# imager-adc.net
KiCad netlist of a schematic drawn in EAGLE
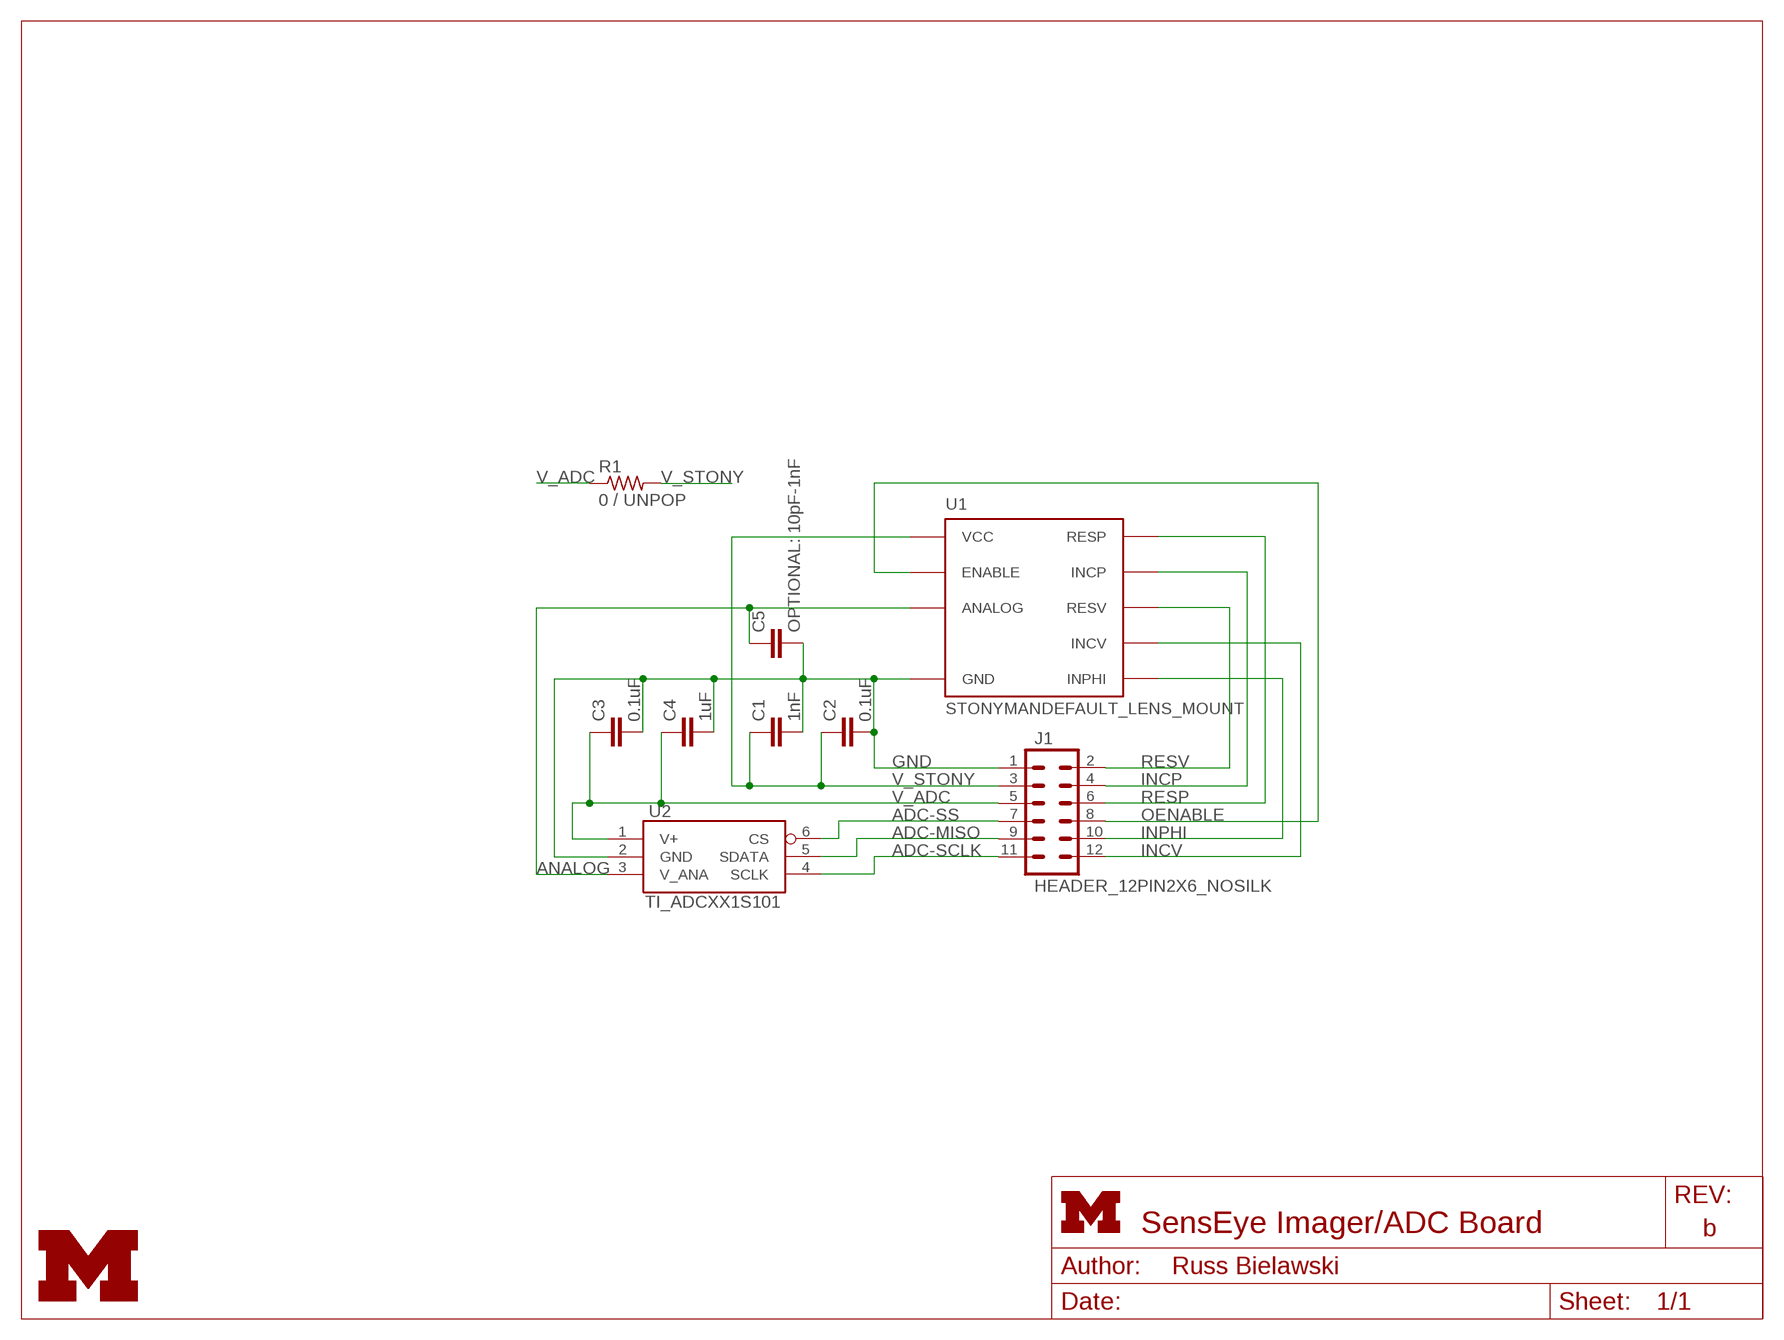
[diagram p0: schematic, sheet 1]

(export (version "E")
  (design (tool "Eeschema 10.0.6"))
  (components
    (comp (ref "C1")
      (value "1nF")
      (footprint "eagle-import:C0603")
      (libsource (lib "eagle-import") (part "C-EUC0603"))
    )
    (comp (ref "C2")
      (value "0.1uF")
      (footprint "eagle-import:C0603")
      (libsource (lib "eagle-import") (part "C-EUC0603"))
    )
    (comp (ref "C3")
      (value "0.1uF")
      (footprint "eagle-import:C0603")
      (libsource (lib "eagle-import") (part "C-EUC0603"))
    )
    (comp (ref "C4")
      (value "1uF")
      (footprint "eagle-import:C0603")
      (libsource (lib "eagle-import") (part "C-EUC0603"))
    )
    (comp (ref "C5")
      (value "OPTIONAL: 10pF-1nF")
      (footprint "eagle-import:C0603")
      (libsource (lib "eagle-import") (part "C-EUC0603"))
    )
    (comp (ref "J1")
      (value "HEADER_12PIN2X6_NOSILK")
      (footprint "eagle-import:HEADER2X6_0.05IN_NO_SILK")
      (libsource (lib "eagle-import") (part "HEADER_12PIN2X6_NOSILK"))
    )
    (comp (ref "R1")
      (value "0 / UNPOP")
      (footprint "eagle-import:R0603")
      (libsource (lib "eagle-import") (part "R-US_R0603"))
    )
    (comp (ref "U$1")
      (value "UMICH_SOLID_SMALL")
      (footprint "eagle-import:UMICH_SOLID_75MIL")
      (libsource (lib "eagle-import") (part "UMICH_SOLID_SMALL"))
    )
    (comp (ref "U1")
      (value "STONYMANDEFAULT_LENS_MOUNT")
      (footprint "eagle-import:STONYMAN_DEFAULT_LENS")
      (libsource (lib "eagle-import") (part "STONYMANDEFAULT_LENS_MOUNT"))
    )
    (comp (ref "U2")
      (value "TI_ADCXX1S101")
      (footprint "eagle-import:SOT23-6")
      (libsource (lib "eagle-import") (part "TI_ADCXX1S101"))
    )
  )
  (nets
    (net (code "1") (name "/ADC-MISO") (class "Default")
      (node (ref "J1") (pin "9") (pinfunction "9_9") (pintype "passive"))
      (node (ref "U2") (pin "5") (pinfunction "SDATA_5") (pintype "bidirectional"))
    )
    (net (code "2") (name "/ADC-SCLK") (class "Default")
      (node (ref "J1") (pin "11") (pinfunction "11_11") (pintype "passive"))
      (node (ref "U2") (pin "4") (pinfunction "SCLK_4") (pintype "bidirectional"))
    )
    (net (code "3") (name "/ADC-SS") (class "Default")
      (node (ref "J1") (pin "7") (pinfunction "7_7") (pintype "passive"))
      (node (ref "U2") (pin "6") (pinfunction "CS_6") (pintype "bidirectional"))
    )
    (net (code "4") (name "/ANALOG") (class "Default")
      (node (ref "C5") (pin "1") (pinfunction "1_1") (pintype "passive"))
      (node (ref "U1") (pin "P$8") (pinfunction "ANALOG_P$8") (pintype "output"))
      (node (ref "U2") (pin "3") (pinfunction "V_ANA_3") (pintype "bidirectional"))
    )
    (net (code "5") (name "/GND") (class "Default")
      (node (ref "C1") (pin "2") (pinfunction "2_2") (pintype "passive"))
      (node (ref "C2") (pin "2") (pinfunction "2_2") (pintype "passive"))
      (node (ref "C3") (pin "2") (pinfunction "2_2") (pintype "passive"))
      (node (ref "C4") (pin "2") (pinfunction "2_2") (pintype "passive"))
      (node (ref "C5") (pin "2") (pinfunction "2_2") (pintype "passive"))
      (node (ref "J1") (pin "1") (pinfunction "1_1") (pintype "passive"))
      (node (ref "U1") (pin "P$1") (pinfunction "GND_P$1") (pintype "power_in"))
      (node (ref "U1") (pin "P$10") (pinfunction "GND_P$10") (pintype "power_in"))
      (node (ref "U2") (pin "2") (pinfunction "GND_2") (pintype "bidirectional"))
    )
    (net (code "6") (name "/INCP") (class "Default")
      (node (ref "J1") (pin "4") (pinfunction "4_4") (pintype "passive"))
      (node (ref "U1") (pin "P$4") (pinfunction "INCP_P$4") (pintype "input"))
    )
    (net (code "7") (name "/INCV") (class "Default")
      (node (ref "J1") (pin "12") (pinfunction "12_12") (pintype "passive"))
      (node (ref "U1") (pin "P$6") (pinfunction "INCV_P$6") (pintype "input"))
    )
    (net (code "8") (name "/INPHI") (class "Default")
      (node (ref "J1") (pin "10") (pinfunction "10_10") (pintype "passive"))
      (node (ref "U1") (pin "P$7") (pinfunction "INPHI_P$7") (pintype "input"))
    )
    (net (code "9") (name "/OENABLE") (class "Default")
      (node (ref "J1") (pin "8") (pinfunction "8_8") (pintype "passive"))
      (node (ref "U1") (pin "P$9") (pinfunction "ENABLE_P$9") (pintype "input"))
    )
    (net (code "10") (name "/RESP") (class "Default")
      (node (ref "J1") (pin "6") (pinfunction "6_6") (pintype "passive"))
      (node (ref "U1") (pin "P$3") (pinfunction "RESP_P$3") (pintype "input"))
    )
    (net (code "11") (name "/RESV") (class "Default")
      (node (ref "J1") (pin "2") (pinfunction "2_2") (pintype "passive"))
      (node (ref "U1") (pin "P$5") (pinfunction "RESV_P$5") (pintype "input"))
    )
    (net (code "12") (name "/V_ADC") (class "Default")
      (node (ref "C3") (pin "1") (pinfunction "1_1") (pintype "passive"))
      (node (ref "C4") (pin "1") (pinfunction "1_1") (pintype "passive"))
      (node (ref "J1") (pin "5") (pinfunction "5_5") (pintype "passive"))
      (node (ref "R1") (pin "1") (pinfunction "1_1") (pintype "passive"))
      (node (ref "U2") (pin "1") (pinfunction "V+_1") (pintype "bidirectional"))
    )
    (net (code "13") (name "/V_STONY") (class "Default")
      (node (ref "C1") (pin "1") (pinfunction "1_1") (pintype "passive"))
      (node (ref "C2") (pin "1") (pinfunction "1_1") (pintype "passive"))
      (node (ref "J1") (pin "3") (pinfunction "3_3") (pintype "passive"))
      (node (ref "R1") (pin "2") (pinfunction "2_2") (pintype "passive"))
      (node (ref "U1") (pin "P$2") (pinfunction "VCC_P$2") (pintype "power_in"))
    )
  )
)
